# Power24V.net
KiCad netlist of a schematic drawn in Altium Designer
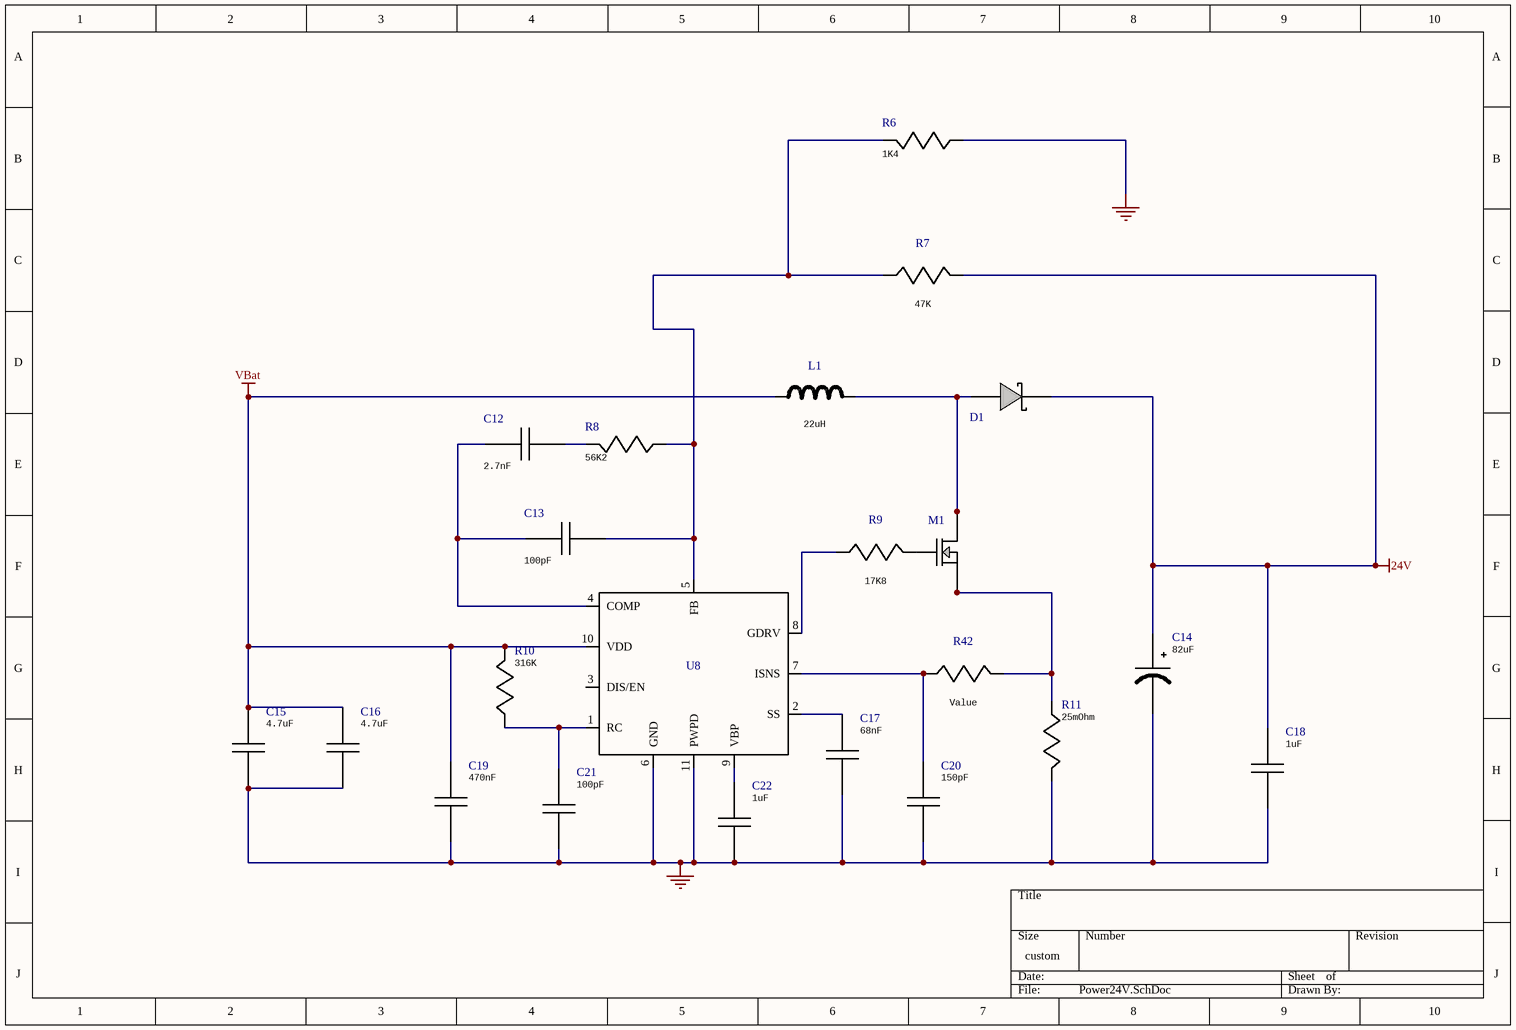
[diagram p0: Power24V.SchDoc]

(export (version "E")
  (design (tool "Eeschema 10.0.6"))
  (components
    (comp (ref "C12")
      (value "2.7nF")
      (footprint "1608")
      (description "Imported")
      (fields
        (field (name "MANUFACTURER_PART_NUMBER") "CC0805KRX7R9BB272")
        (field (name "Comment") "CC0805KRX7R9BB27")
      )
      (libsource (lib "TI WEBENCH") (part "CC0805KRX7R9BB27"))
    )
    (comp (ref "C13")
      (value "100pF")
      (footprint "1608")
      (description "Imported")
      (fields
        (field (name "MANUFACTURER_PART_NUMBER") "CC0805JRNPO9BN101")
        (field (name "Comment") "CC0805JRNPO9BN10")
      )
      (libsource (lib "TI WEBENCH") (part "CC0805JRNPO9BN10"))
    )
    (comp (ref "C14")
      (value "82uF")
      (footprint "CAPSMT_62_E12")
      (description "Imported")
      (fields (field (name "MANUFACTURER_PART_NUMBER") "35SVPF82M"))
      (libsource (lib "TI WEBENCH") (part "35SVPF82M"))
    )
    (comp (ref "C15")
      (value "4.7uF")
      (footprint "0805")
      (description "Imported")
      (fields
        (field (name "MANUFACTURER_PART_NUMBER") "GRM21BR61E475MA12L")
        (field (name "Comment") "GRM21BR61E475MA1")
      )
      (libsource (lib "TI WEBENCH") (part "GRM21BR61E475MA1"))
    )
    (comp (ref "C16")
      (value "4.7uF")
      (footprint "0805")
      (description "Imported")
      (fields
        (field (name "MANUFACTURER_PART_NUMBER") "GRM21BR61E475MA12L")
        (field (name "Comment") "GRM21BR61E475MA1")
      )
      (libsource (lib "TI WEBENCH") (part "GRM21BR61E475MA1"))
    )
    (comp (ref "C17")
      (value "68nF")
      (footprint "1608")
      (description "Imported")
      (fields
        (field (name "MANUFACTURER_PART_NUMBER") "GRM155R61A683KA01D")
        (field (name "Comment") "GRM155R61A683KA0")
      )
      (libsource (lib "TI WEBENCH") (part "GRM155R61A683KA0"))
    )
    (comp (ref "C18")
      (value "1uF")
      (footprint "0805")
      (description "Imported")
      (fields (field (name "MANUFACTURER_PART_NUMBER") "GMK212B7105KG-T"))
      (libsource (lib "TI WEBENCH") (part "GMK212B7105KG-T"))
    )
    (comp (ref "C19")
      (value "470nF")
      (footprint "0805")
      (description "Imported")
      (fields (field (name "MANUFACTURER_PART_NUMBER") "EMK212B7474KD-T"))
      (libsource (lib "TI WEBENCH") (part "EMK212B7474KD-T"))
    )
    (comp (ref "C20")
      (value "150pF")
      (footprint "0805")
      (description "Imported")
      (fields
        (field (name "MANUFACTURER_PART_NUMBER") "CC0805JRNPO9BN151")
        (field (name "Comment") "CC0805JRNPO9BN15")
      )
      (libsource (lib "TI WEBENCH") (part "CC0805JRNPO9BN15"))
    )
    (comp (ref "C21")
      (value "100pF")
      (footprint "1608")
      (description "Imported")
      (fields
        (field (name "MANUFACTURER_PART_NUMBER") "CC0805JRNPO9BN101")
        (field (name "Comment") "CC0805JRNPO9BN10")
      )
      (libsource (lib "TI WEBENCH") (part "CC0805JRNPO9BN10"))
    )
    (comp (ref "C22")
      (value "1uF")
      (footprint "1608")
      (description "Imported")
      (fields (field (name "MANUFACTURER_PART_NUMBER") "C1608X5R1C105K"))
      (libsource (lib "TI WEBENCH") (part "C1608X5R1C105K"))
    )
    (comp (ref "D1")
      (value "B240A-13-F")
      (footprint "SMA")
      (description "Imported")
      (libsource (lib "TI WEBENCH") (part "B240A-13-F"))
    )
    (comp (ref "L1")
      (value "22uH")
      (footprint "SRR1210")
      (description "Imported")
      (fields (field (name "MANUFACTURER_PART_NUMBER") "SRR1210-220M"))
      (libsource (lib "TI WEBENCH") (part "SRR1210-220M"))
    )
    (comp (ref "M1")
      (value "CSD17551Q5A")
      (footprint "TRANS_NexFET_Q5A")
      (description "Imported")
      (libsource (lib "TI WEBENCH") (part "CSD17551Q5A"))
    )
    (comp (ref "R6")
      (value "1K4")
      (footprint "1608")
      (description "Imported")
      (fields (field (name "MANUFACTURER_PART_NUMBER") "CRCW04021K40FKED"))
      (libsource (lib "TI WEBENCH") (part "CRCW04021K40FKED"))
    )
    (comp (ref "R7")
      (value "47K")
      (footprint "1608")
      (description "Imported")
      (fields (field (name "MANUFACTURER_PART_NUMBER") "RR1220P-473-D"))
      (libsource (lib "TI WEBENCH") (part "RR1220P-473-D"))
    )
    (comp (ref "R8")
      (value "56K2")
      (footprint "1608")
      (description "Imported")
      (fields (field (name "MANUFACTURER_PART_NUMBER") "CRCW040256K2FKED"))
      (libsource (lib "TI WEBENCH") (part "CRCW040256K2FKED"))
    )
    (comp (ref "R9")
      (value "17K8")
      (footprint "1608")
      (description "Imported")
      (fields (field (name "MANUFACTURER_PART_NUMBER") "CRCW040217R8FKED"))
      (libsource (lib "TI WEBENCH") (part "CRCW040217R8FKED"))
    )
    (comp (ref "R10")
      (value "316K")
      (footprint "1608")
      (description "Imported")
      (fields (field (name "MANUFACTURER_PART_NUMBER") "CRCW0402316KFKED"))
      (libsource (lib "TI WEBENCH") (part "CRCW0402316KFKED"))
    )
    (comp (ref "R11")
      (value "25mOhm")
      (footprint "1206")
      (description "Imported")
      (fields (field (name "MANUFACTURER_PART_NUMBER") "CSR1206FK25L0"))
      (libsource (lib "TI WEBENCH") (part "CSR1206FK25L0"))
    )
    (comp (ref "R42")
      (value "Value")
      (footprint "1608")
      (description "Riflt")
      (fields (field (name "MANUFACTURER_PART_NUMBER") "CRCW04021K00FKED"))
      (libsource (lib "TI WEBENCH") (part "CRCW04021K00FKED"))
    )
    (comp (ref "U8")
      (value "TPS40210DGQR")
      (footprint "S-PDSO-G10")
      (description "Imported")
      (libsource (lib "TI WEBENCH") (part "TPS40210DGQR"))
    )
  )
  (nets
    (net (code "1") (name "24V") (class "Default")
      (node (ref "C14") (pin "1") (pinfunction "+_1") (pintype "passive"))
      (node (ref "C18") (pin "1") (pinfunction "1_1") (pintype "passive"))
      (node (ref "D1") (pin "1") (pinfunction "K_1") (pintype "passive"))
      (node (ref "R7") (pin "1") (pinfunction "1_1") (pintype "passive"))
    )
    (net (code "2") (name "GND") (class "Default")
      (node (ref "C14") (pin "2") (pinfunction "-_2") (pintype "passive"))
      (node (ref "C15") (pin "2") (pinfunction "2_2") (pintype "passive"))
      (node (ref "C16") (pin "2") (pinfunction "2_2") (pintype "passive"))
      (node (ref "C17") (pin "2") (pinfunction "2_2") (pintype "passive"))
      (node (ref "C18") (pin "2") (pinfunction "2_2") (pintype "passive"))
      (node (ref "C19") (pin "2") (pinfunction "2_2") (pintype "passive"))
      (node (ref "C20") (pin "2") (pinfunction "2_2") (pintype "passive"))
      (node (ref "C21") (pin "2") (pinfunction "2_2") (pintype "passive"))
      (node (ref "C22") (pin "2") (pinfunction "2_2") (pintype "passive"))
      (node (ref "R11") (pin "1") (pinfunction "1_1") (pintype "passive"))
      (node (ref "R6") (pin "2") (pinfunction "2_2") (pintype "passive"))
      (node (ref "U8") (pin "11") (pinfunction "PWPD_11") (pintype "passive"))
      (node (ref "U8") (pin "6") (pinfunction "GND_6") (pintype "passive"))
    )
    (net (code "3") (name "Net-(C12-Pad2)") (class "Default")
      (node (ref "C12") (pin "2") (pinfunction "2_2") (pintype "passive"))
      (node (ref "R8") (pin "1") (pinfunction "1_1") (pintype "passive"))
    )
    (net (code "4") (name "Net-(D1-A)") (class "Default")
      (node (ref "D1") (pin "2") (pinfunction "A_2") (pintype "passive"))
      (node (ref "L1") (pin "2") (pinfunction "2_2") (pintype "passive"))
      (node (ref "M1") (pin "5") (pinfunction "Drain_5") (pintype "passive"))
      (node (ref "M1") (pin "6") (pinfunction "Drain_6") (pintype "passive"))
      (node (ref "M1") (pin "7") (pinfunction "Drain_7") (pintype "passive"))
      (node (ref "M1") (pin "8") (pinfunction "Drain_8") (pintype "passive"))
      (node (ref "M1") (pin "9") (pinfunction "Drain_9") (pintype "passive"))
    )
    (net (code "5") (name "Net-(M1-Gate)") (class "Default")
      (node (ref "M1") (pin "4") (pinfunction "Gate_4") (pintype "passive"))
      (node (ref "R9") (pin "1") (pinfunction "1_1") (pintype "passive"))
    )
    (net (code "6") (name "Net-(M1-Source-Pad1)") (class "Default")
      (node (ref "M1") (pin "1") (pinfunction "Source_1") (pintype "passive"))
      (node (ref "M1") (pin "2") (pinfunction "Source_2") (pintype "passive"))
      (node (ref "M1") (pin "3") (pinfunction "Source_3") (pintype "passive"))
      (node (ref "R11") (pin "2") (pinfunction "2_2") (pintype "passive"))
      (node (ref "R42") (pin "1") (pinfunction "1_1") (pintype "passive"))
    )
    (net (code "7") (name "Net-(U8-COMP)") (class "Default")
      (node (ref "C12") (pin "1") (pinfunction "1_1") (pintype "passive"))
      (node (ref "C13") (pin "1") (pinfunction "1_1") (pintype "passive"))
      (node (ref "U8") (pin "4") (pinfunction "COMP_4") (pintype "passive"))
    )
    (net (code "8") (name "Net-(U8-FB)") (class "Default")
      (node (ref "C13") (pin "2") (pinfunction "2_2") (pintype "passive"))
      (node (ref "R6") (pin "1") (pinfunction "1_1") (pintype "passive"))
      (node (ref "R7") (pin "2") (pinfunction "2_2") (pintype "passive"))
      (node (ref "R8") (pin "2") (pinfunction "2_2") (pintype "passive"))
      (node (ref "U8") (pin "5") (pinfunction "FB_5") (pintype "passive"))
    )
    (net (code "9") (name "Net-(U8-GDRV)") (class "Default")
      (node (ref "R9") (pin "2") (pinfunction "2_2") (pintype "passive"))
      (node (ref "U8") (pin "8") (pinfunction "GDRV_8") (pintype "passive"))
    )
    (net (code "10") (name "Net-(U8-ISNS)") (class "Default")
      (node (ref "C20") (pin "1") (pinfunction "1_1") (pintype "passive"))
      (node (ref "R42") (pin "2") (pinfunction "2_2") (pintype "passive"))
      (node (ref "U8") (pin "7") (pinfunction "ISNS_7") (pintype "passive"))
    )
    (net (code "11") (name "Net-(U8-RC)") (class "Default")
      (node (ref "C21") (pin "1") (pinfunction "1_1") (pintype "passive"))
      (node (ref "R10") (pin "2") (pinfunction "2_2") (pintype "passive"))
      (node (ref "U8") (pin "1") (pinfunction "RC_1") (pintype "passive"))
    )
    (net (code "12") (name "Net-(U8-SS)") (class "Default")
      (node (ref "C17") (pin "1") (pinfunction "1_1") (pintype "passive"))
      (node (ref "U8") (pin "2") (pinfunction "SS_2") (pintype "passive"))
    )
    (net (code "13") (name "Net-(U8-VBP)") (class "Default")
      (node (ref "C22") (pin "1") (pinfunction "1_1") (pintype "passive"))
      (node (ref "U8") (pin "9") (pinfunction "VBP_9") (pintype "passive"))
    )
    (net (code "14") (name "VBat") (class "Default")
      (node (ref "C15") (pin "1") (pinfunction "1_1") (pintype "passive"))
      (node (ref "C16") (pin "1") (pinfunction "1_1") (pintype "passive"))
      (node (ref "C19") (pin "1") (pinfunction "1_1") (pintype "passive"))
      (node (ref "L1") (pin "1") (pinfunction "1_1") (pintype "passive"))
      (node (ref "R10") (pin "1") (pinfunction "1_1") (pintype "passive"))
      (node (ref "U8") (pin "10") (pinfunction "VDD_10") (pintype "passive"))
    )
    (net (code "15") (name "unconnected-(U8-DIS{slash}EN-Pad3)") (class "Default")
      (node (ref "U8") (pin "3") (pinfunction "DIS/EN_3") (pintype "passive"))
    )
  )
)
